# ft2232d.net
KiCad netlist of a schematic drawn in Altium Designer
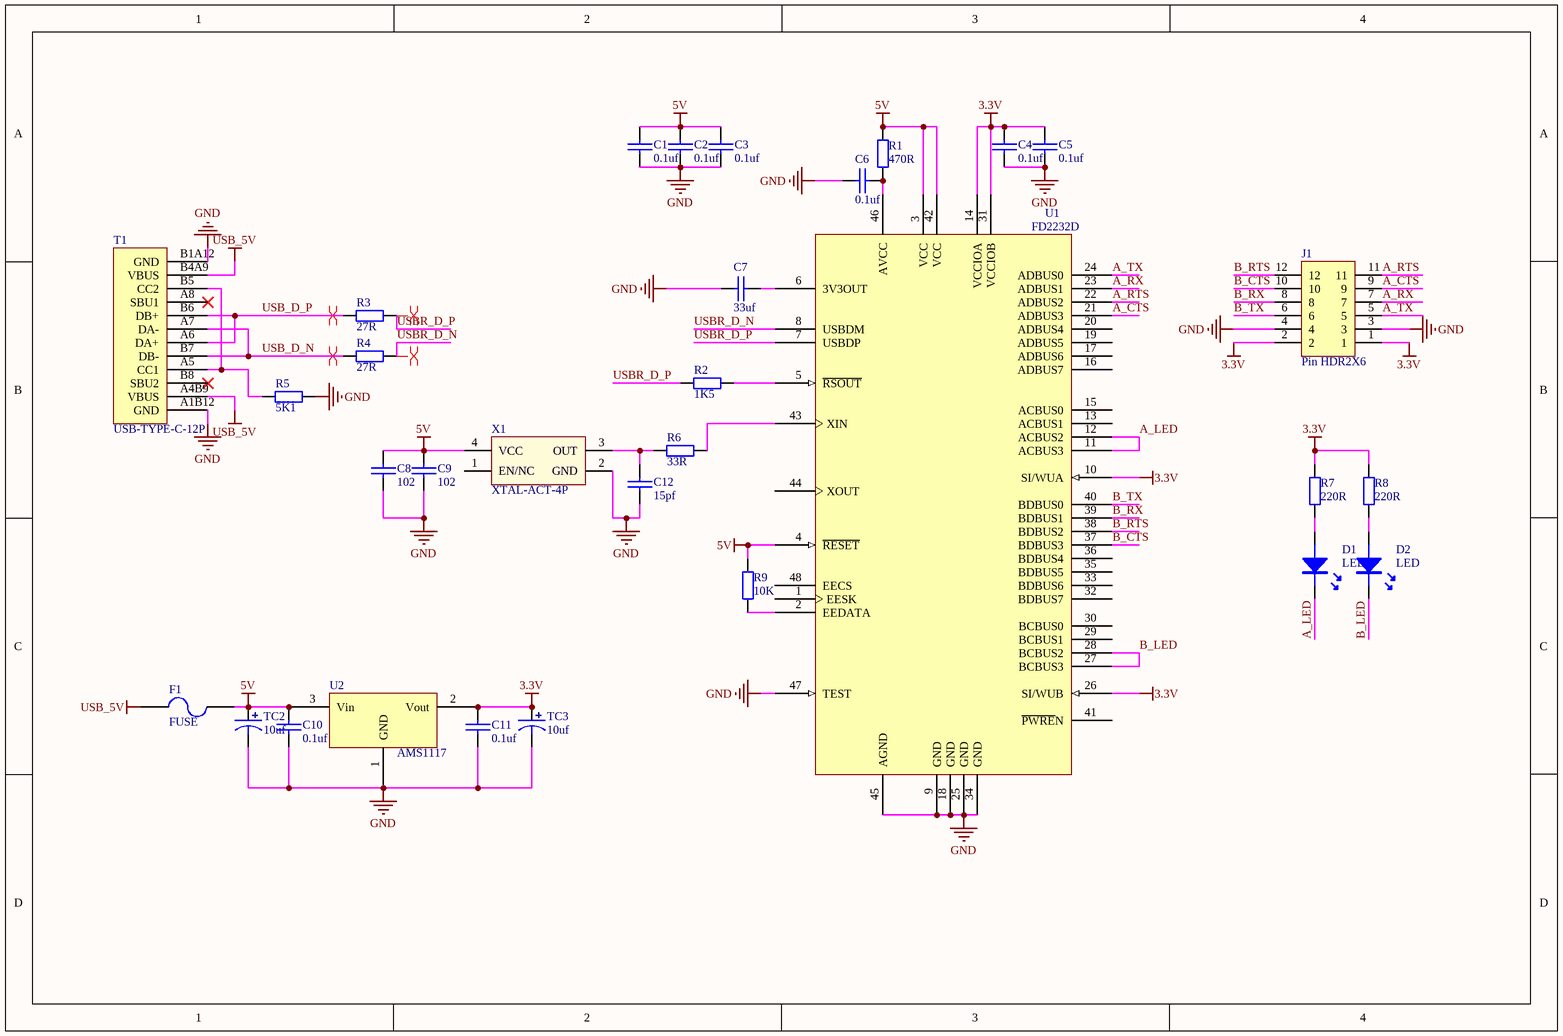
[diagram p0: ft2232d.SchDoc]

(export (version "E")
  (design (tool "Eeschema 10.0.6"))
  (components
    (comp (ref "C1")
      (value "0.1uf")
      (footprint "0603C")
      (description "无极性电容")
      (libsource (lib "电容") (part "CAP"))
    )
    (comp (ref "C2")
      (value "0.1uf")
      (footprint "0603C")
      (description "无极性电容")
      (libsource (lib "电容") (part "CAP"))
    )
    (comp (ref "C3")
      (value "0.1uf")
      (footprint "0603C")
      (description "无极性电容")
      (libsource (lib "电容") (part "CAP"))
    )
    (comp (ref "C4")
      (value "0.1uf")
      (footprint "0603C")
      (description "无极性电容")
      (libsource (lib "电容") (part "CAP"))
    )
    (comp (ref "C5")
      (value "0.1uf")
      (footprint "0603C")
      (description "无极性电容")
      (libsource (lib "电容") (part "CAP"))
    )
    (comp (ref "C6")
      (value "0.1uf")
      (footprint "0603C")
      (description "无极性电容")
      (libsource (lib "电容") (part "CAP"))
    )
    (comp (ref "C7")
      (value "33uf")
      (footprint "0603C")
      (description "无极性电容")
      (libsource (lib "电容") (part "CAP"))
    )
    (comp (ref "C8")
      (value "102")
      (footprint "0603C")
      (description "无极性电容")
      (libsource (lib "电容") (part "CAP"))
    )
    (comp (ref "C9")
      (value "102")
      (footprint "0603C")
      (description "无极性电容")
      (libsource (lib "电容") (part "CAP"))
    )
    (comp (ref "C10")
      (value "0.1uf")
      (footprint "0603C")
      (description "无极性电容")
      (libsource (lib "电容") (part "CAP"))
    )
    (comp (ref "C11")
      (value "0.1uf")
      (footprint "0603C")
      (description "无极性电容")
      (libsource (lib "电容") (part "CAP"))
    )
    (comp (ref "C12")
      (value "15pf")
      (footprint "0603C")
      (description "无极性电容")
      (libsource (lib "电容") (part "CAP"))
    )
    (comp (ref "D1") (value "LED") (footprint "LED-0603B") (libsource (lib "LED") (part "LED")))
    (comp (ref "D2") (value "LED") (footprint "LED-0603B") (libsource (lib "LED") (part "LED")))
    (comp (ref "F1") (value "FUSE") (footprint "FUSE-1210") (libsource (lib "保险丝") (part "FUSE")))
    (comp (ref "J1")
      (value "Pin HDR2X6")
      (footprint "Pin HDR2X6/2.54mm-S")
      (libsource (lib "排针") (part "Pin HDR2X6"))
    )
    (comp (ref "R1")
      (value "470R")
      (footprint "0603R")
      (description "贴片电阻")
      (libsource (lib "") (part "RES_1"))
    )
    (comp (ref "R2")
      (value "1K5")
      (footprint "0603R")
      (description "贴片电阻")
      (libsource (lib "电阻") (part "RES"))
    )
    (comp (ref "R3")
      (value "27R")
      (footprint "0603R")
      (description "贴片电阻")
      (libsource (lib "Miscellaneous Base") (part "RES"))
    )
    (comp (ref "R4")
      (value "27R")
      (footprint "0603R")
      (description "贴片电阻")
      (libsource (lib "Miscellaneous Base") (part "RES"))
    )
    (comp (ref "R5")
      (value "5K1")
      (footprint "0603R")
      (description "贴片电阻")
      (libsource (lib "Miscellaneous Base") (part "RES"))
    )
    (comp (ref "R6")
      (value "33R")
      (footprint "0603R")
      (description "贴片电阻")
      (libsource (lib "Miscellaneous Base") (part "RES"))
    )
    (comp (ref "R7")
      (value "220R")
      (footprint "0603R")
      (description "贴片电阻")
      (libsource (lib "") (part "RES_1"))
    )
    (comp (ref "R8")
      (value "220R")
      (footprint "0603R")
      (description "贴片电阻")
      (libsource (lib "") (part "RES_1"))
    )
    (comp (ref "R9")
      (value "10K")
      (footprint "0603R")
      (description "贴片电阻")
      (libsource (lib "") (part "RES_1"))
    )
    (comp (ref "T1")
      (value "USB-TYPE-C-12P")
      (footprint "type-c-12p")
      (libsource (lib "USB") (part "USB-TYPE-C-12P"))
    )
    (comp (ref "TC2")
      (value "10uf")
      (footprint "TAJ-A/3216")
      (description "钽电容")
      (libsource (lib "电容") (part "TCAP"))
    )
    (comp (ref "TC3")
      (value "10uf")
      (footprint "TAJ-A/3216")
      (description "钽电容")
      (libsource (lib "电容") (part "TCAP"))
    )
    (comp (ref "U1") (value "FD2232D") (footprint "LQFP48 7X7") (libsource (lib "Mylib") (part "FD2232D")))
    (comp (ref "U2")
      (value "AMS1117")
      (footprint "SOT223")
      (description "三端稳压芯片")
      (libsource (lib "电源芯片") (part "AMS1117"))
    )
    (comp (ref "X1")
      (value "XTAL-ACT-4P")
      (footprint "OSC-5032-4P-2")
      (description "4脚有源晶振")
      (libsource (lib "晶振") (part "XTAL-ACT-4P"))
    )
  )
  (nets
    (net (code "1") (name "/A_CTS") (class "Default")
      (node (ref "J1") (pin "9") (pinfunction "9_9") (pintype "passive"))
      (node (ref "U1") (pin "21") (pinfunction "ADBUS3_21") (pintype "passive"))
    )
    (net (code "2") (name "/A_LED") (class "Default")
      (node (ref "D1") (pin "K") (pinfunction "K_K") (pintype "passive"))
      (node (ref "U1") (pin "11") (pinfunction "ACBUS3_11") (pintype "passive"))
      (node (ref "U1") (pin "12") (pinfunction "ACBUS2_12") (pintype "passive"))
    )
    (net (code "3") (name "/A_RTS") (class "Default")
      (node (ref "J1") (pin "11") (pinfunction "11_11") (pintype "passive"))
      (node (ref "U1") (pin "22") (pinfunction "ADBUS2_22") (pintype "passive"))
    )
    (net (code "4") (name "/A_RX") (class "Default")
      (node (ref "J1") (pin "7") (pinfunction "7_7") (pintype "passive"))
      (node (ref "U1") (pin "23") (pinfunction "ADBUS1_23") (pintype "passive"))
    )
    (net (code "5") (name "/A_TX") (class "Default")
      (node (ref "J1") (pin "5") (pinfunction "5_5") (pintype "passive"))
      (node (ref "U1") (pin "24") (pinfunction "ADBUS0_24") (pintype "passive"))
    )
    (net (code "6") (name "/B_CTS") (class "Default")
      (node (ref "J1") (pin "10") (pinfunction "10_10") (pintype "passive"))
      (node (ref "U1") (pin "37") (pinfunction "BDBUS3_37") (pintype "passive"))
    )
    (net (code "7") (name "/B_LED") (class "Default")
      (node (ref "D2") (pin "K") (pinfunction "K_K") (pintype "passive"))
      (node (ref "U1") (pin "27") (pinfunction "BCBUS3_27") (pintype "passive"))
      (node (ref "U1") (pin "28") (pinfunction "BCBUS2_28") (pintype "passive"))
    )
    (net (code "8") (name "/B_RTS") (class "Default")
      (node (ref "J1") (pin "12") (pinfunction "12_12") (pintype "passive"))
      (node (ref "U1") (pin "38") (pinfunction "BDBUS2_38") (pintype "passive"))
    )
    (net (code "9") (name "/B_RX") (class "Default")
      (node (ref "J1") (pin "8") (pinfunction "8_8") (pintype "passive"))
      (node (ref "U1") (pin "39") (pinfunction "BDBUS1_39") (pintype "passive"))
    )
    (net (code "10") (name "/B_TX") (class "Default")
      (node (ref "J1") (pin "6") (pinfunction "6_6") (pintype "passive"))
      (node (ref "U1") (pin "40") (pinfunction "BDBUS0_40") (pintype "passive"))
    )
    (net (code "11") (name "/USBR_D_N") (class "Default")
      (node (ref "R4") (pin "1") (pinfunction "1_1") (pintype "passive"))
      (node (ref "U1") (pin "8") (pinfunction "USBDM_8") (pintype "passive"))
    )
    (net (code "12") (name "/USBR_D_P") (class "Default")
      (node (ref "R2") (pin "2") (pinfunction "2_2") (pintype "passive"))
      (node (ref "R3") (pin "1") (pinfunction "1_1") (pintype "passive"))
      (node (ref "U1") (pin "7") (pinfunction "USBDP_7") (pintype "passive"))
    )
    (net (code "13") (name "/USB_D_N") (class "Default")
      (node (ref "R4") (pin "2") (pinfunction "2_2") (pintype "passive"))
      (node (ref "T1") (pin "A7") (pinfunction "DA-_A7") (pintype "passive"))
      (node (ref "T1") (pin "B7") (pinfunction "DB-_B7") (pintype "passive"))
    )
    (net (code "14") (name "/USB_D_P") (class "Default")
      (node (ref "R3") (pin "2") (pinfunction "2_2") (pintype "passive"))
      (node (ref "T1") (pin "A6") (pinfunction "DA+_A6") (pintype "passive"))
      (node (ref "T1") (pin "B6") (pinfunction "DB+_B6") (pintype "passive"))
    )
    (net (code "15") (name "3.3V") (class "Default")
      (node (ref "C11") (pin "2") (pinfunction "2_2") (pintype "passive"))
      (node (ref "C4") (pin "2") (pinfunction "2_2") (pintype "passive"))
      (node (ref "C5") (pin "2") (pinfunction "2_2") (pintype "passive"))
      (node (ref "J1") (pin "1") (pinfunction "1_1") (pintype "passive"))
      (node (ref "J1") (pin "2") (pinfunction "2_2") (pintype "passive"))
      (node (ref "R7") (pin "1") (pinfunction "1_1") (pintype "passive"))
      (node (ref "R8") (pin "1") (pinfunction "1_1") (pintype "passive"))
      (node (ref "TC3") (pin "1") (pinfunction "1_1") (pintype "passive"))
      (node (ref "U1") (pin "10") (pinfunction "SI/WUA_10") (pintype "input"))
      (node (ref "U1") (pin "14") (pinfunction "VCCIOA_14") (pintype "passive"))
      (node (ref "U1") (pin "26") (pinfunction "SI/WUB_26") (pintype "input"))
      (node (ref "U1") (pin "31") (pinfunction "VCCIOB_31") (pintype "passive"))
      (node (ref "U2") (pin "2") (pinfunction "Vout_2") (pintype "passive"))
    )
    (net (code "16") (name "5V") (class "Default")
      (node (ref "C1") (pin "2") (pinfunction "2_2") (pintype "passive"))
      (node (ref "C10") (pin "2") (pinfunction "2_2") (pintype "passive"))
      (node (ref "C2") (pin "2") (pinfunction "2_2") (pintype "passive"))
      (node (ref "C3") (pin "2") (pinfunction "2_2") (pintype "passive"))
      (node (ref "C8") (pin "2") (pinfunction "2_2") (pintype "passive"))
      (node (ref "C9") (pin "2") (pinfunction "2_2") (pintype "passive"))
      (node (ref "F1") (pin "2") (pinfunction "2_2") (pintype "passive"))
      (node (ref "R1") (pin "1") (pinfunction "1_1") (pintype "passive"))
      (node (ref "R9") (pin "1") (pinfunction "1_1") (pintype "passive"))
      (node (ref "TC2") (pin "1") (pinfunction "1_1") (pintype "passive"))
      (node (ref "U1") (pin "3") (pinfunction "VCC_3") (pintype "power_in"))
      (node (ref "U1") (pin "4") (pinfunction "~{RESET}_4") (pintype "input"))
      (node (ref "U1") (pin "42") (pinfunction "VCC_42") (pintype "power_in"))
      (node (ref "U2") (pin "3") (pinfunction "Vin_3") (pintype "passive"))
      (node (ref "X1") (pin "4") (pinfunction "VCC_4") (pintype "passive"))
    )
    (net (code "17") (name "GND") (class "Default")
      (node (ref "C1") (pin "1") (pinfunction "1_1") (pintype "passive"))
      (node (ref "C10") (pin "1") (pinfunction "1_1") (pintype "passive"))
      (node (ref "C11") (pin "1") (pinfunction "1_1") (pintype "passive"))
      (node (ref "C12") (pin "1") (pinfunction "1_1") (pintype "passive"))
      (node (ref "C2") (pin "1") (pinfunction "1_1") (pintype "passive"))
      (node (ref "C3") (pin "1") (pinfunction "1_1") (pintype "passive"))
      (node (ref "C4") (pin "1") (pinfunction "1_1") (pintype "passive"))
      (node (ref "C5") (pin "1") (pinfunction "1_1") (pintype "passive"))
      (node (ref "C6") (pin "2") (pinfunction "2_2") (pintype "passive"))
      (node (ref "C7") (pin "2") (pinfunction "2_2") (pintype "passive"))
      (node (ref "C8") (pin "1") (pinfunction "1_1") (pintype "passive"))
      (node (ref "C9") (pin "1") (pinfunction "1_1") (pintype "passive"))
      (node (ref "J1") (pin "3") (pinfunction "3_3") (pintype "passive"))
      (node (ref "J1") (pin "4") (pinfunction "4_4") (pintype "passive"))
      (node (ref "R5") (pin "1") (pinfunction "1_1") (pintype "passive"))
      (node (ref "T1") (pin "A1B12") (pinfunction "GND_A1B12") (pintype "passive"))
      (node (ref "T1") (pin "B1A12") (pinfunction "GND_B1A12") (pintype "passive"))
      (node (ref "TC2") (pin "2") (pinfunction "2_2") (pintype "passive"))
      (node (ref "TC3") (pin "2") (pinfunction "2_2") (pintype "passive"))
      (node (ref "U1") (pin "18") (pinfunction "GND_18") (pintype "passive"))
      (node (ref "U1") (pin "25") (pinfunction "GND_25") (pintype "power_in"))
      (node (ref "U1") (pin "34") (pinfunction "GND_34") (pintype "power_in"))
      (node (ref "U1") (pin "45") (pinfunction "AGND_45") (pintype "power_in"))
      (node (ref "U1") (pin "47") (pinfunction "TEST_47") (pintype "input"))
      (node (ref "U1") (pin "9") (pinfunction "GND_9") (pintype "power_in"))
      (node (ref "U2") (pin "1") (pinfunction "GND_1") (pintype "passive"))
      (node (ref "X1") (pin "2") (pinfunction "GND_2") (pintype "passive"))
    )
    (net (code "18") (name "Net-(D1-PadA)") (class "Default")
      (node (ref "D1") (pin "A") (pinfunction "A_A") (pintype "passive"))
      (node (ref "R7") (pin "2") (pinfunction "2_2") (pintype "passive"))
    )
    (net (code "19") (name "Net-(D2-PadA)") (class "Default")
      (node (ref "D2") (pin "A") (pinfunction "A_A") (pintype "passive"))
      (node (ref "R8") (pin "2") (pinfunction "2_2") (pintype "passive"))
    )
    (net (code "20") (name "Net-(T1-CC1)") (class "Default")
      (node (ref "R5") (pin "2") (pinfunction "2_2") (pintype "passive"))
      (node (ref "T1") (pin "A5") (pinfunction "CC1_A5") (pintype "passive"))
      (node (ref "T1") (pin "B5") (pinfunction "CC2_B5") (pintype "passive"))
    )
    (net (code "21") (name "Net-(U1-3V3OUT)") (class "Default")
      (node (ref "C7") (pin "1") (pinfunction "1_1") (pintype "passive"))
      (node (ref "U1") (pin "6") (pinfunction "3V3OUT_6") (pintype "power_in"))
    )
    (net (code "22") (name "Net-(U1-AVCC)") (class "Default")
      (node (ref "C6") (pin "1") (pinfunction "1_1") (pintype "passive"))
      (node (ref "R1") (pin "2") (pinfunction "2_2") (pintype "passive"))
      (node (ref "U1") (pin "46") (pinfunction "AVCC_46") (pintype "power_in"))
    )
    (net (code "23") (name "Net-(U1-EEDATA)") (class "Default")
      (node (ref "R9") (pin "2") (pinfunction "2_2") (pintype "passive"))
      (node (ref "U1") (pin "2") (pinfunction "EEDATA_2") (pintype "passive"))
    )
    (net (code "24") (name "Net-(U1-XIN)") (class "Default")
      (node (ref "R6") (pin "1") (pinfunction "1_1") (pintype "passive"))
      (node (ref "U1") (pin "43") (pinfunction "XIN_43") (pintype "passive"))
    )
    (net (code "25") (name "Net-(U1-~{RSOUT})") (class "Default")
      (node (ref "R2") (pin "1") (pinfunction "1_1") (pintype "passive"))
      (node (ref "U1") (pin "5") (pinfunction "~{RSOUT}_5") (pintype "input"))
    )
    (net (code "26") (name "Net-(X1-OUT)") (class "Default")
      (node (ref "C12") (pin "2") (pinfunction "2_2") (pintype "passive"))
      (node (ref "R6") (pin "2") (pinfunction "2_2") (pintype "passive"))
      (node (ref "X1") (pin "3") (pinfunction "OUT_3") (pintype "passive"))
    )
    (net (code "27") (name "USB_5V") (class "Default")
      (node (ref "F1") (pin "1") (pinfunction "1_1") (pintype "passive"))
      (node (ref "T1") (pin "A4B9") (pinfunction "VBUS_A4B9") (pintype "passive"))
      (node (ref "T1") (pin "B4A9") (pinfunction "VBUS_B4A9") (pintype "passive"))
    )
    (net (code "28") (name "unconnected-(T1-SBU1-PadA8)") (class "Default")
      (node (ref "T1") (pin "A8") (pinfunction "SBU1_A8") (pintype "passive+no_connect"))
    )
    (net (code "29") (name "unconnected-(T1-SBU2-PadB8)") (class "Default")
      (node (ref "T1") (pin "B8") (pinfunction "SBU2_B8") (pintype "passive+no_connect"))
    )
    (net (code "30") (name "unconnected-(U1-ACBUS0-Pad15)") (class "Default")
      (node (ref "U1") (pin "15") (pinfunction "ACBUS0_15") (pintype "passive"))
    )
    (net (code "31") (name "unconnected-(U1-ACBUS1-Pad13)") (class "Default")
      (node (ref "U1") (pin "13") (pinfunction "ACBUS1_13") (pintype "passive"))
    )
    (net (code "32") (name "unconnected-(U1-ADBUS4-Pad20)") (class "Default")
      (node (ref "U1") (pin "20") (pinfunction "ADBUS4_20") (pintype "passive"))
    )
    (net (code "33") (name "unconnected-(U1-ADBUS5-Pad19)") (class "Default")
      (node (ref "U1") (pin "19") (pinfunction "ADBUS5_19") (pintype "passive"))
    )
    (net (code "34") (name "unconnected-(U1-ADBUS6-Pad17)") (class "Default")
      (node (ref "U1") (pin "17") (pinfunction "ADBUS6_17") (pintype "passive"))
    )
    (net (code "35") (name "unconnected-(U1-ADBUS7-Pad16)") (class "Default")
      (node (ref "U1") (pin "16") (pinfunction "ADBUS7_16") (pintype "passive"))
    )
    (net (code "36") (name "unconnected-(U1-BCBUS0-Pad30)") (class "Default")
      (node (ref "U1") (pin "30") (pinfunction "BCBUS0_30") (pintype "passive"))
    )
    (net (code "37") (name "unconnected-(U1-BCBUS1-Pad29)") (class "Default")
      (node (ref "U1") (pin "29") (pinfunction "BCBUS1_29") (pintype "passive"))
    )
    (net (code "38") (name "unconnected-(U1-BDBUS4-Pad36)") (class "Default")
      (node (ref "U1") (pin "36") (pinfunction "BDBUS4_36") (pintype "passive"))
    )
    (net (code "39") (name "unconnected-(U1-BDBUS5-Pad35)") (class "Default")
      (node (ref "U1") (pin "35") (pinfunction "BDBUS5_35") (pintype "passive"))
    )
    (net (code "40") (name "unconnected-(U1-BDBUS6-Pad33)") (class "Default")
      (node (ref "U1") (pin "33") (pinfunction "BDBUS6_33") (pintype "passive"))
    )
    (net (code "41") (name "unconnected-(U1-BDBUS7-Pad32)") (class "Default")
      (node (ref "U1") (pin "32") (pinfunction "BDBUS7_32") (pintype "passive"))
    )
    (net (code "42") (name "unconnected-(U1-EECS-Pad48)") (class "Default")
      (node (ref "U1") (pin "48") (pinfunction "EECS_48") (pintype "passive"))
    )
    (net (code "43") (name "unconnected-(U1-EESK-Pad1)") (class "Default")
      (node (ref "U1") (pin "1") (pinfunction "EESK_1") (pintype "passive"))
    )
    (net (code "44") (name "unconnected-(U1-XOUT-Pad44)") (class "Default")
      (node (ref "U1") (pin "44") (pinfunction "XOUT_44") (pintype "passive"))
    )
    (net (code "45") (name "unconnected-(U1-~{PWRE}N-Pad41)") (class "Default")
      (node (ref "U1") (pin "41") (pinfunction "~{PWRE}N_41") (pintype "passive"))
    )
    (net (code "46") (name "unconnected-(X1-EN{slash}NC-Pad1)") (class "Default")
      (node (ref "X1") (pin "1") (pinfunction "EN/NC_1") (pintype "passive"))
    )
  )
)
